# SensorAddOn.net
KiCad netlist of a schematic drawn in Altium Designer
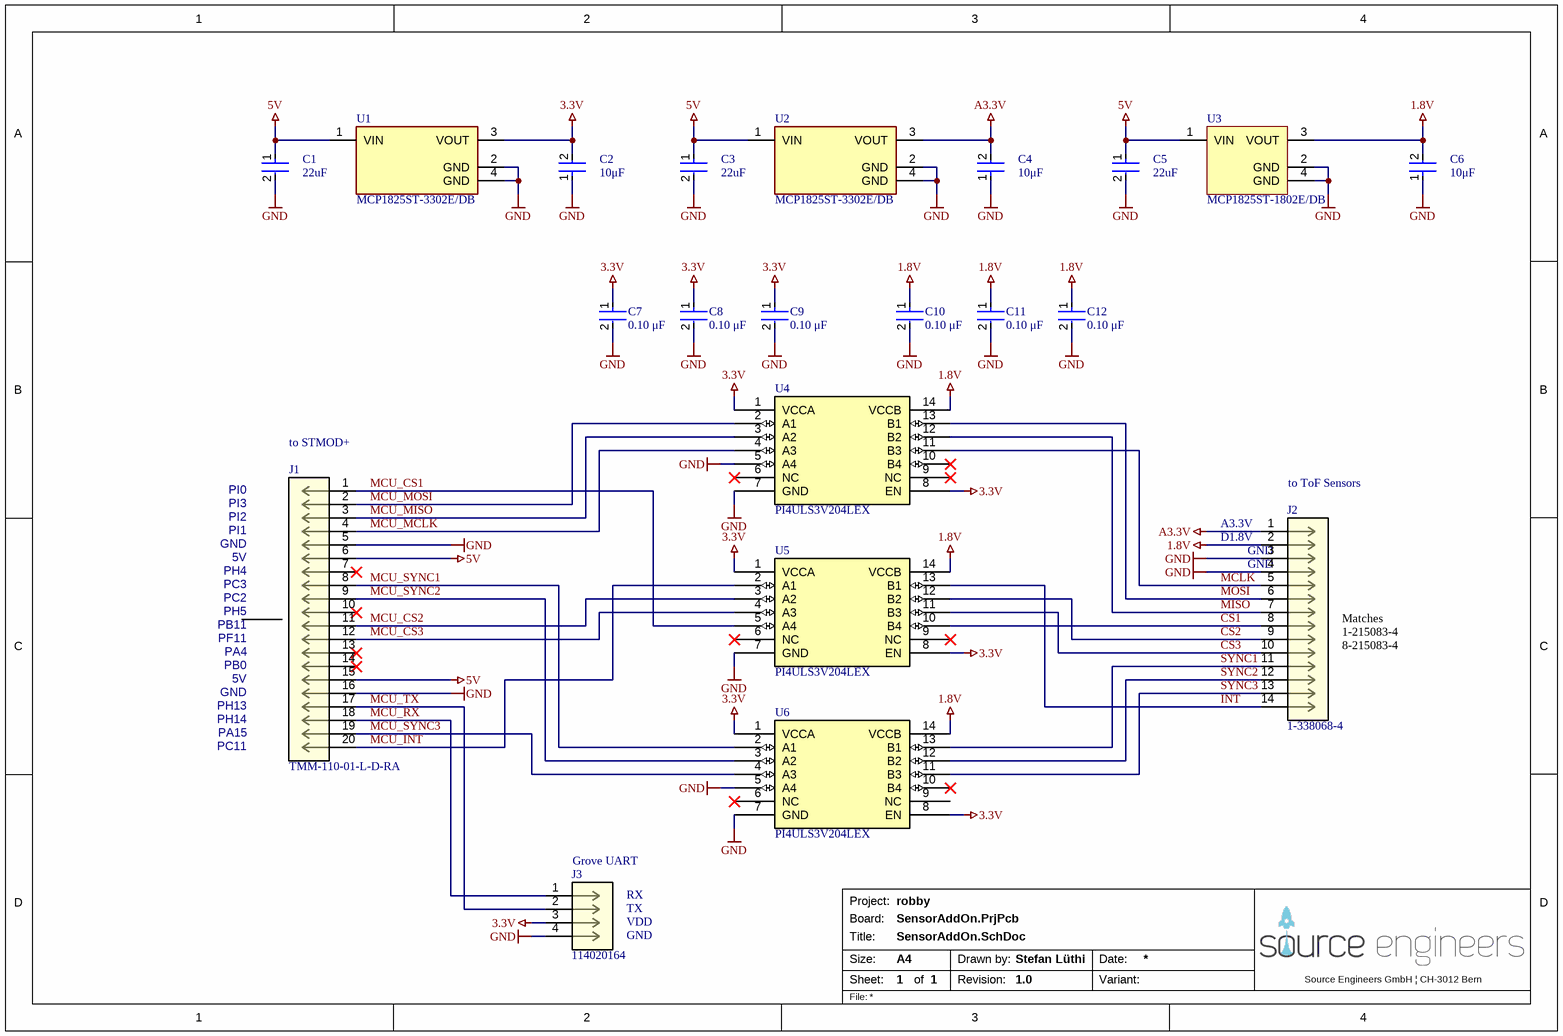
[diagram p0: SensorAddOn.SchDoc]

(export (version "E")
  (design (tool "Eeschema 10.0.6"))
  (components
    (comp (ref "C1")
      (value "GRM319R61C226ME15D")
      (footprint "FP-GRM319-0_15-IPC_C")
      (description "Chip Multilayer Ceramic Capacitors for General Purpose, 1206, 22uF, X5R, 15%, 20%, 16V")
      (fields (field (name "TOLERANCE") "20%") (field (name "CAPACITANCE") "22uF"))
      (libsource (lib "Altium Content Vault") (part "b4654b650e69147ec39a6b967a45e02"))
    )
    (comp (ref "C2")
      (value "10μF")
      (footprint "FP-GRM31C-0_2-e0_3_0_8-IPC_B")
      (description "Chip Multilayer Ceramic Capacitors for General Purpose, 1206, 10uF, X7R, 15%, 20%, 25V")
      (fields (field (name "Comment") "GRM31CR71E106MA12K"))
      (libsource (lib "Altium Content Vault") (part "02cd4be3c70576c341d710602a673aa"))
    )
    (comp (ref "C3")
      (value "GRM319R61C226ME15D")
      (footprint "FP-GRM319-0_15-IPC_C")
      (description "Chip Multilayer Ceramic Capacitors for General Purpose, 1206, 22uF, X5R, 15%, 20%, 16V")
      (fields (field (name "TOLERANCE") "20%") (field (name "CAPACITANCE") "22uF"))
      (libsource (lib "Altium Content Vault") (part "b4654b650e69147ec39a6b967a45e02"))
    )
    (comp (ref "C4")
      (value "10μF")
      (footprint "FP-GRM31C-0_2-e0_3_0_8-IPC_B")
      (description "Chip Multilayer Ceramic Capacitors for General Purpose, 1206, 10uF, X7R, 15%, 20%, 25V")
      (fields (field (name "Comment") "GRM31CR71E106MA12K"))
      (libsource (lib "Altium Content Vault") (part "02cd4be3c70576c341d710602a673aa"))
    )
    (comp (ref "C5")
      (value "GRM319R61C226ME15D")
      (footprint "FP-GRM319-0_15-IPC_C")
      (description "Chip Multilayer Ceramic Capacitors for General Purpose, 1206, 22uF, X5R, 15%, 20%, 16V")
      (fields (field (name "TOLERANCE") "20%") (field (name "CAPACITANCE") "22uF"))
      (libsource (lib "Altium Content Vault") (part "b4654b650e69147ec39a6b967a45e02"))
    )
    (comp (ref "C6")
      (value "10μF")
      (footprint "FP-GRM31C-0_2-e0_3_0_8-IPC_B")
      (description "Chip Multilayer Ceramic Capacitors for General Purpose, 1206, 10uF, X7R, 15%, 20%, 25V")
      (fields (field (name "Comment") "GRM31CR71E106MA12K"))
      (libsource (lib "Altium Content Vault") (part "02cd4be3c70576c341d710602a673aa"))
    )
    (comp (ref "C7")
      (value "0.10 μF")
      (footprint "FP-C0603C-CF-MFG")
      (description "CAP CER 0.1UF 50V 20% X7R 0603")
      (fields
        (field (name "MANUFACTURER PART NUMBER") "C0603C104M5RACTU")
        (field (name "MANUFACTURER") "KEMET")
      )
      (libsource (lib "Altium Content Vault") (part "b4654b650e69147ec39a6b967a45e02"))
    )
    (comp (ref "C8")
      (value "0.10 μF")
      (footprint "FP-C0603C-CF-MFG")
      (description "CAP CER 0.1UF 50V 20% X7R 0603")
      (fields
        (field (name "MANUFACTURER PART NUMBER") "C0603C104M5RACTU")
        (field (name "MANUFACTURER") "KEMET")
      )
      (libsource (lib "Altium Content Vault") (part "b4654b650e69147ec39a6b967a45e02"))
    )
    (comp (ref "C9")
      (value "0.10 μF")
      (footprint "FP-C0603C-CF-MFG")
      (description "CAP CER 0.1UF 50V 20% X7R 0603")
      (fields
        (field (name "MANUFACTURER PART NUMBER") "C0603C104M5RACTU")
        (field (name "MANUFACTURER") "KEMET")
      )
      (libsource (lib "Altium Content Vault") (part "b4654b650e69147ec39a6b967a45e02"))
    )
    (comp (ref "C10")
      (value "0.10 μF")
      (footprint "FP-C0603C-CF-MFG")
      (description "CAP CER 0.1UF 50V 20% X7R 0603")
      (fields
        (field (name "MANUFACTURER PART NUMBER") "C0603C104M5RACTU")
        (field (name "MANUFACTURER") "KEMET")
      )
      (libsource (lib "Altium Content Vault") (part "b4654b650e69147ec39a6b967a45e02"))
    )
    (comp (ref "C11")
      (value "0.10 μF")
      (footprint "FP-C0603C-CF-MFG")
      (description "CAP CER 0.1UF 50V 20% X7R 0603")
      (fields
        (field (name "MANUFACTURER PART NUMBER") "C0603C104M5RACTU")
        (field (name "MANUFACTURER") "KEMET")
      )
      (libsource (lib "Altium Content Vault") (part "b4654b650e69147ec39a6b967a45e02"))
    )
    (comp (ref "C12")
      (value "0.10 μF")
      (footprint "FP-C0603C-CF-MFG")
      (description "CAP CER 0.1UF 50V 20% X7R 0603")
      (fields
        (field (name "MANUFACTURER PART NUMBER") "C0603C104M5RACTU")
        (field (name "MANUFACTURER") "KEMET")
      )
      (libsource (lib "Altium Content Vault") (part "b4654b650e69147ec39a6b967a45e02"))
    )
    (comp (ref "J1")
      (value "TMM-110-01-L-D-RA")
      (footprint "CONN_TMM-110-XX-XX-D-RA_SAI")
      (description "No Description Available")
      (fields (field (name "COPYRIGHT") "Copyright (C) 2025 Ultra Librarian. All rights reserved."))
      (libsource (lib "robby") (part "TMM-110-01-L-D-RA"))
    )
    (comp (ref "J2")
      (value "1-338068-4")
      (footprint "CONN_1-338068-4_TYC")
      (description "MICRO-MATCH FTE,14P")
      (fields (field (name "COPYRIGHT") "Copyright (C) 2025 Ultra Librarian. All rights reserved."))
      (libsource (lib "robby") (part "1-338068-4"))
    )
    (comp (ref "J3")
      (value "114020164")
      (footprint "CONN4_20164_SEE")
      (description "No Description Available")
      (fields (field (name "COPYRIGHT") "Copyright (C) 2025 Ultra Librarian. All rights reserved."))
      (libsource (lib "robby") (part "114020164"))
    )
    (comp (ref "U1")
      (value "MCP1825ST-3302E/DB")
      (footprint "FP-C04-032-MFG")
      (description "IC REG LIN 3.3V 500MA SOT223-3")
      (libsource (lib "Altium Content Vault") (part "c835a22949432570081152522179a5e"))
    )
    (comp (ref "U2")
      (value "MCP1825ST-3302E/DB")
      (footprint "FP-C04-032-MFG")
      (description "IC REG LIN 3.3V 500MA SOT223-3")
      (libsource (lib "Altium Content Vault") (part "c835a22949432570081152522179a5e"))
    )
    (comp (ref "U3")
      (value "MCP1825ST-1802E/DB")
      (footprint "SOT-223-DB3_N")
      (libsource (lib "Altium Content Vault") (part "PM-LINEREG-MCP1825-IL4"))
    )
    (comp (ref "U4")
      (value "PI4ULS3V204LEX")
      (footprint "SOIC_3V204LEX_DIO")
      (description "Description")
      (fields (field (name "COPYRIGHT") "Copyright (C) 2025 Ultra Librarian. All rights reserved."))
      (libsource (lib "robby") (part "PI4ULS3V204LEX"))
    )
    (comp (ref "U5")
      (value "PI4ULS3V204LEX")
      (footprint "SOIC_3V204LEX_DIO")
      (description "Description")
      (fields (field (name "COPYRIGHT") "Copyright (C) 2025 Ultra Librarian. All rights reserved."))
      (libsource (lib "robby") (part "PI4ULS3V204LEX"))
    )
    (comp (ref "U6")
      (value "PI4ULS3V204LEX")
      (footprint "SOIC_3V204LEX_DIO")
      (description "Description")
      (fields (field (name "COPYRIGHT") "Copyright (C) 2025 Ultra Librarian. All rights reserved."))
      (libsource (lib "robby") (part "PI4ULS3V204LEX"))
    )
  )
  (nets
    (net (code "1") (name "/CS1") (class "Default")
      (node (ref "J2") (pin "8") (pinfunction "8_8") (pintype "passive"))
      (node (ref "U5") (pin "10") (pinfunction "B4_10") (pintype "bidirectional"))
    )
    (net (code "2") (name "/CS2") (class "Default")
      (node (ref "J2") (pin "9") (pinfunction "9_9") (pintype "passive"))
      (node (ref "U5") (pin "12") (pinfunction "B2_12") (pintype "bidirectional"))
    )
    (net (code "3") (name "/CS3") (class "Default")
      (node (ref "J2") (pin "10") (pinfunction "10_10") (pintype "passive"))
      (node (ref "U5") (pin "11") (pinfunction "B3_11") (pintype "bidirectional"))
    )
    (net (code "4") (name "/MCLK") (class "Default")
      (node (ref "J2") (pin "5") (pinfunction "5_5") (pintype "passive"))
      (node (ref "U4") (pin "11") (pinfunction "B3_11") (pintype "bidirectional"))
    )
    (net (code "5") (name "/MCU_CS1") (class "Default")
      (node (ref "J1") (pin "1") (pinfunction "1_1") (pintype "passive"))
      (node (ref "U5") (pin "5") (pinfunction "A4_5") (pintype "bidirectional"))
    )
    (net (code "6") (name "/MCU_CS2") (class "Default")
      (node (ref "J1") (pin "11") (pinfunction "11_11") (pintype "passive"))
      (node (ref "U5") (pin "3") (pinfunction "A2_3") (pintype "bidirectional"))
    )
    (net (code "7") (name "/MCU_CS3") (class "Default")
      (node (ref "J1") (pin "12") (pinfunction "12_12") (pintype "passive"))
      (node (ref "U5") (pin "4") (pinfunction "A3_4") (pintype "bidirectional"))
    )
    (net (code "8") (name "/MCU_MCLK") (class "Default")
      (node (ref "J1") (pin "4") (pinfunction "4_4") (pintype "passive"))
      (node (ref "U4") (pin "4") (pinfunction "A3_4") (pintype "bidirectional"))
    )
    (net (code "9") (name "/MCU_MISO") (class "Default")
      (node (ref "J1") (pin "3") (pinfunction "3_3") (pintype "passive"))
      (node (ref "U4") (pin "3") (pinfunction "A2_3") (pintype "bidirectional"))
    )
    (net (code "10") (name "/MCU_MOSI") (class "Default")
      (node (ref "J1") (pin "2") (pinfunction "2_2") (pintype "passive"))
      (node (ref "U4") (pin "2") (pinfunction "A1_2") (pintype "bidirectional"))
    )
    (net (code "11") (name "/MCU_RX") (class "Default")
      (node (ref "J1") (pin "18") (pinfunction "18_18") (pintype "passive"))
      (node (ref "J3") (pin "1") (pinfunction "1_1") (pintype "passive"))
    )
    (net (code "12") (name "/MCU_SYNC1") (class "Default")
      (node (ref "J1") (pin "8") (pinfunction "8_8") (pintype "passive"))
      (node (ref "U6") (pin "2") (pinfunction "A1_2") (pintype "bidirectional"))
    )
    (net (code "13") (name "/MCU_SYNC2") (class "Default")
      (node (ref "J1") (pin "9") (pinfunction "9_9") (pintype "passive"))
      (node (ref "U6") (pin "3") (pinfunction "A2_3") (pintype "bidirectional"))
    )
    (net (code "14") (name "/MCU_SYNC3") (class "Default")
      (node (ref "J1") (pin "19") (pinfunction "19_19") (pintype "passive"))
      (node (ref "U6") (pin "4") (pinfunction "A3_4") (pintype "bidirectional"))
    )
    (net (code "15") (name "/MCU_TX") (class "Default")
      (node (ref "J1") (pin "17") (pinfunction "17_17") (pintype "passive"))
      (node (ref "J3") (pin "2") (pinfunction "2_2") (pintype "passive"))
    )
    (net (code "16") (name "/MCU_~{INT}") (class "Default")
      (node (ref "J1") (pin "20") (pinfunction "20_20") (pintype "passive"))
      (node (ref "U5") (pin "2") (pinfunction "A1_2") (pintype "bidirectional"))
    )
    (net (code "17") (name "/MISO") (class "Default")
      (node (ref "J2") (pin "7") (pinfunction "7_7") (pintype "passive"))
      (node (ref "U4") (pin "12") (pinfunction "B2_12") (pintype "bidirectional"))
    )
    (net (code "18") (name "/MOSI") (class "Default")
      (node (ref "J2") (pin "6") (pinfunction "6_6") (pintype "passive"))
      (node (ref "U4") (pin "13") (pinfunction "B1_13") (pintype "bidirectional"))
    )
    (net (code "19") (name "/SYNC1") (class "Default")
      (node (ref "J2") (pin "11") (pinfunction "11_11") (pintype "passive"))
      (node (ref "U6") (pin "13") (pinfunction "B1_13") (pintype "bidirectional"))
    )
    (net (code "20") (name "/SYNC2") (class "Default")
      (node (ref "J2") (pin "12") (pinfunction "12_12") (pintype "passive"))
      (node (ref "U6") (pin "12") (pinfunction "B2_12") (pintype "bidirectional"))
    )
    (net (code "21") (name "/SYNC3") (class "Default")
      (node (ref "J2") (pin "13") (pinfunction "13_13") (pintype "passive"))
      (node (ref "U6") (pin "11") (pinfunction "B3_11") (pintype "bidirectional"))
    )
    (net (code "22") (name "/~{INT}") (class "Default")
      (node (ref "J2") (pin "14") (pinfunction "14_14") (pintype "passive"))
      (node (ref "U5") (pin "13") (pinfunction "B1_13") (pintype "bidirectional"))
    )
    (net (code "23") (name "1.8V") (class "Default")
      (node (ref "C10") (pin "1") (pinfunction "1_1") (pintype "passive"))
      (node (ref "C11") (pin "1") (pinfunction "1_1") (pintype "passive"))
      (node (ref "C12") (pin "1") (pinfunction "1_1") (pintype "passive"))
      (node (ref "C6") (pin "2") (pinfunction "2_2") (pintype "passive"))
      (node (ref "J2") (pin "2") (pinfunction "2_2") (pintype "passive"))
      (node (ref "U3") (pin "3") (pinfunction "VOUT_3") (pintype "power_in"))
      (node (ref "U4") (pin "14") (pinfunction "VCCB_14") (pintype "power_in"))
      (node (ref "U5") (pin "14") (pinfunction "VCCB_14") (pintype "power_in"))
      (node (ref "U6") (pin "14") (pinfunction "VCCB_14") (pintype "power_in"))
    )
    (net (code "24") (name "3.3V") (class "Default")
      (node (ref "C2") (pin "2") (pinfunction "2_2") (pintype "passive"))
      (node (ref "C7") (pin "1") (pinfunction "1_1") (pintype "passive"))
      (node (ref "C8") (pin "1") (pinfunction "1_1") (pintype "passive"))
      (node (ref "C9") (pin "1") (pinfunction "1_1") (pintype "passive"))
      (node (ref "J3") (pin "3") (pinfunction "3_3") (pintype "passive"))
      (node (ref "U1") (pin "3") (pinfunction "VOUT_3") (pintype "power_in"))
      (node (ref "U4") (pin "1") (pinfunction "VCCA_1") (pintype "power_in"))
      (node (ref "U4") (pin "8") (pinfunction "EN_8") (pintype "passive"))
      (node (ref "U5") (pin "1") (pinfunction "VCCA_1") (pintype "power_in"))
      (node (ref "U5") (pin "8") (pinfunction "EN_8") (pintype "passive"))
      (node (ref "U6") (pin "1") (pinfunction "VCCA_1") (pintype "power_in"))
      (node (ref "U6") (pin "8") (pinfunction "EN_8") (pintype "passive"))
    )
    (net (code "25") (name "5V") (class "Default")
      (node (ref "C1") (pin "1") (pinfunction "1_1") (pintype "passive"))
      (node (ref "C3") (pin "1") (pinfunction "1_1") (pintype "passive"))
      (node (ref "C5") (pin "1") (pinfunction "1_1") (pintype "passive"))
      (node (ref "J1") (pin "15") (pinfunction "15_15") (pintype "passive"))
      (node (ref "J1") (pin "6") (pinfunction "6_6") (pintype "passive"))
      (node (ref "U1") (pin "1") (pinfunction "VIN_1") (pintype "power_in"))
      (node (ref "U2") (pin "1") (pinfunction "VIN_1") (pintype "power_in"))
      (node (ref "U3") (pin "1") (pinfunction "VIN_1") (pintype "power_in"))
    )
    (net (code "26") (name "A3.3V") (class "Default")
      (node (ref "C4") (pin "2") (pinfunction "2_2") (pintype "passive"))
      (node (ref "J2") (pin "1") (pinfunction "1_1") (pintype "passive"))
      (node (ref "U2") (pin "3") (pinfunction "VOUT_3") (pintype "power_in"))
    )
    (net (code "27") (name "GND") (class "Default")
      (node (ref "C1") (pin "2") (pinfunction "2_2") (pintype "passive"))
      (node (ref "C10") (pin "2") (pinfunction "2_2") (pintype "passive"))
      (node (ref "C11") (pin "2") (pinfunction "2_2") (pintype "passive"))
      (node (ref "C12") (pin "2") (pinfunction "2_2") (pintype "passive"))
      (node (ref "C2") (pin "1") (pinfunction "1_1") (pintype "passive"))
      (node (ref "C3") (pin "2") (pinfunction "2_2") (pintype "passive"))
      (node (ref "C4") (pin "1") (pinfunction "1_1") (pintype "passive"))
      (node (ref "C5") (pin "2") (pinfunction "2_2") (pintype "passive"))
      (node (ref "C6") (pin "1") (pinfunction "1_1") (pintype "passive"))
      (node (ref "C7") (pin "2") (pinfunction "2_2") (pintype "passive"))
      (node (ref "C8") (pin "2") (pinfunction "2_2") (pintype "passive"))
      (node (ref "C9") (pin "2") (pinfunction "2_2") (pintype "passive"))
      (node (ref "J1") (pin "16") (pinfunction "16_16") (pintype "passive"))
      (node (ref "J1") (pin "5") (pinfunction "5_5") (pintype "passive"))
      (node (ref "J2") (pin "3") (pinfunction "3_3") (pintype "passive"))
      (node (ref "J2") (pin "4") (pinfunction "4_4") (pintype "passive"))
      (node (ref "J3") (pin "4") (pinfunction "4_4") (pintype "passive"))
      (node (ref "U1") (pin "2") (pinfunction "GND_2") (pintype "power_in"))
      (node (ref "U1") (pin "4") (pinfunction "GND_4") (pintype "power_in"))
      (node (ref "U2") (pin "2") (pinfunction "GND_2") (pintype "power_in"))
      (node (ref "U2") (pin "4") (pinfunction "GND_4") (pintype "power_in"))
      (node (ref "U3") (pin "2") (pinfunction "GND_2") (pintype "power_in"))
      (node (ref "U3") (pin "4") (pinfunction "GND_4") (pintype "power_in"))
      (node (ref "U4") (pin "5") (pinfunction "A4_5") (pintype "bidirectional"))
      (node (ref "U4") (pin "7") (pinfunction "GND_7") (pintype "power_in"))
      (node (ref "U5") (pin "7") (pinfunction "GND_7") (pintype "power_in"))
      (node (ref "U6") (pin "5") (pinfunction "A4_5") (pintype "bidirectional"))
      (node (ref "U6") (pin "7") (pinfunction "GND_7") (pintype "power_in"))
    )
    (net (code "28") (name "unconnected-(J1-Pad7)") (class "Default")
      (node (ref "J1") (pin "7") (pinfunction "7_7") (pintype "passive+no_connect"))
    )
    (net (code "29") (name "unconnected-(J1-Pad10)") (class "Default")
      (node (ref "J1") (pin "10") (pinfunction "10_10") (pintype "passive+no_connect"))
    )
    (net (code "30") (name "unconnected-(J1-Pad13)") (class "Default")
      (node (ref "J1") (pin "13") (pinfunction "13_13") (pintype "passive+no_connect"))
    )
    (net (code "31") (name "unconnected-(J1-Pad14)") (class "Default")
      (node (ref "J1") (pin "14") (pinfunction "14_14") (pintype "passive+no_connect"))
    )
    (net (code "32") (name "unconnected-(U4-B4-Pad10)") (class "Default")
      (node (ref "U4") (pin "10") (pinfunction "B4_10") (pintype "bidirectional+no_connect"))
    )
    (net (code "33") (name "unconnected-(U4-NC-Pad6)") (class "Default")
      (node (ref "U4") (pin "6") (pinfunction "NC_6") (pintype "passive+no_connect"))
    )
    (net (code "34") (name "unconnected-(U4-NC-Pad9)") (class "Default")
      (node (ref "U4") (pin "9") (pinfunction "NC_9") (pintype "passive+no_connect"))
    )
    (net (code "35") (name "unconnected-(U5-NC-Pad6)") (class "Default")
      (node (ref "U5") (pin "6") (pinfunction "NC_6") (pintype "passive+no_connect"))
    )
    (net (code "36") (name "unconnected-(U5-NC-Pad9)") (class "Default")
      (node (ref "U5") (pin "9") (pinfunction "NC_9") (pintype "passive+no_connect"))
    )
    (net (code "37") (name "unconnected-(U6-B4-Pad10)") (class "Default")
      (node (ref "U6") (pin "10") (pinfunction "B4_10") (pintype "bidirectional+no_connect"))
    )
    (net (code "38") (name "unconnected-(U6-NC-Pad6)") (class "Default")
      (node (ref "U6") (pin "6") (pinfunction "NC_6") (pintype "passive+no_connect"))
    )
    (net (code "39") (name "unconnected-(U6-NC-Pad9)") (class "Default")
      (node (ref "U6") (pin "9") (pinfunction "NC_9") (pintype "passive"))
    )
  )
)
